# 04_-_Connectors.net
KiCad netlist of a schematic drawn in Altium Designer
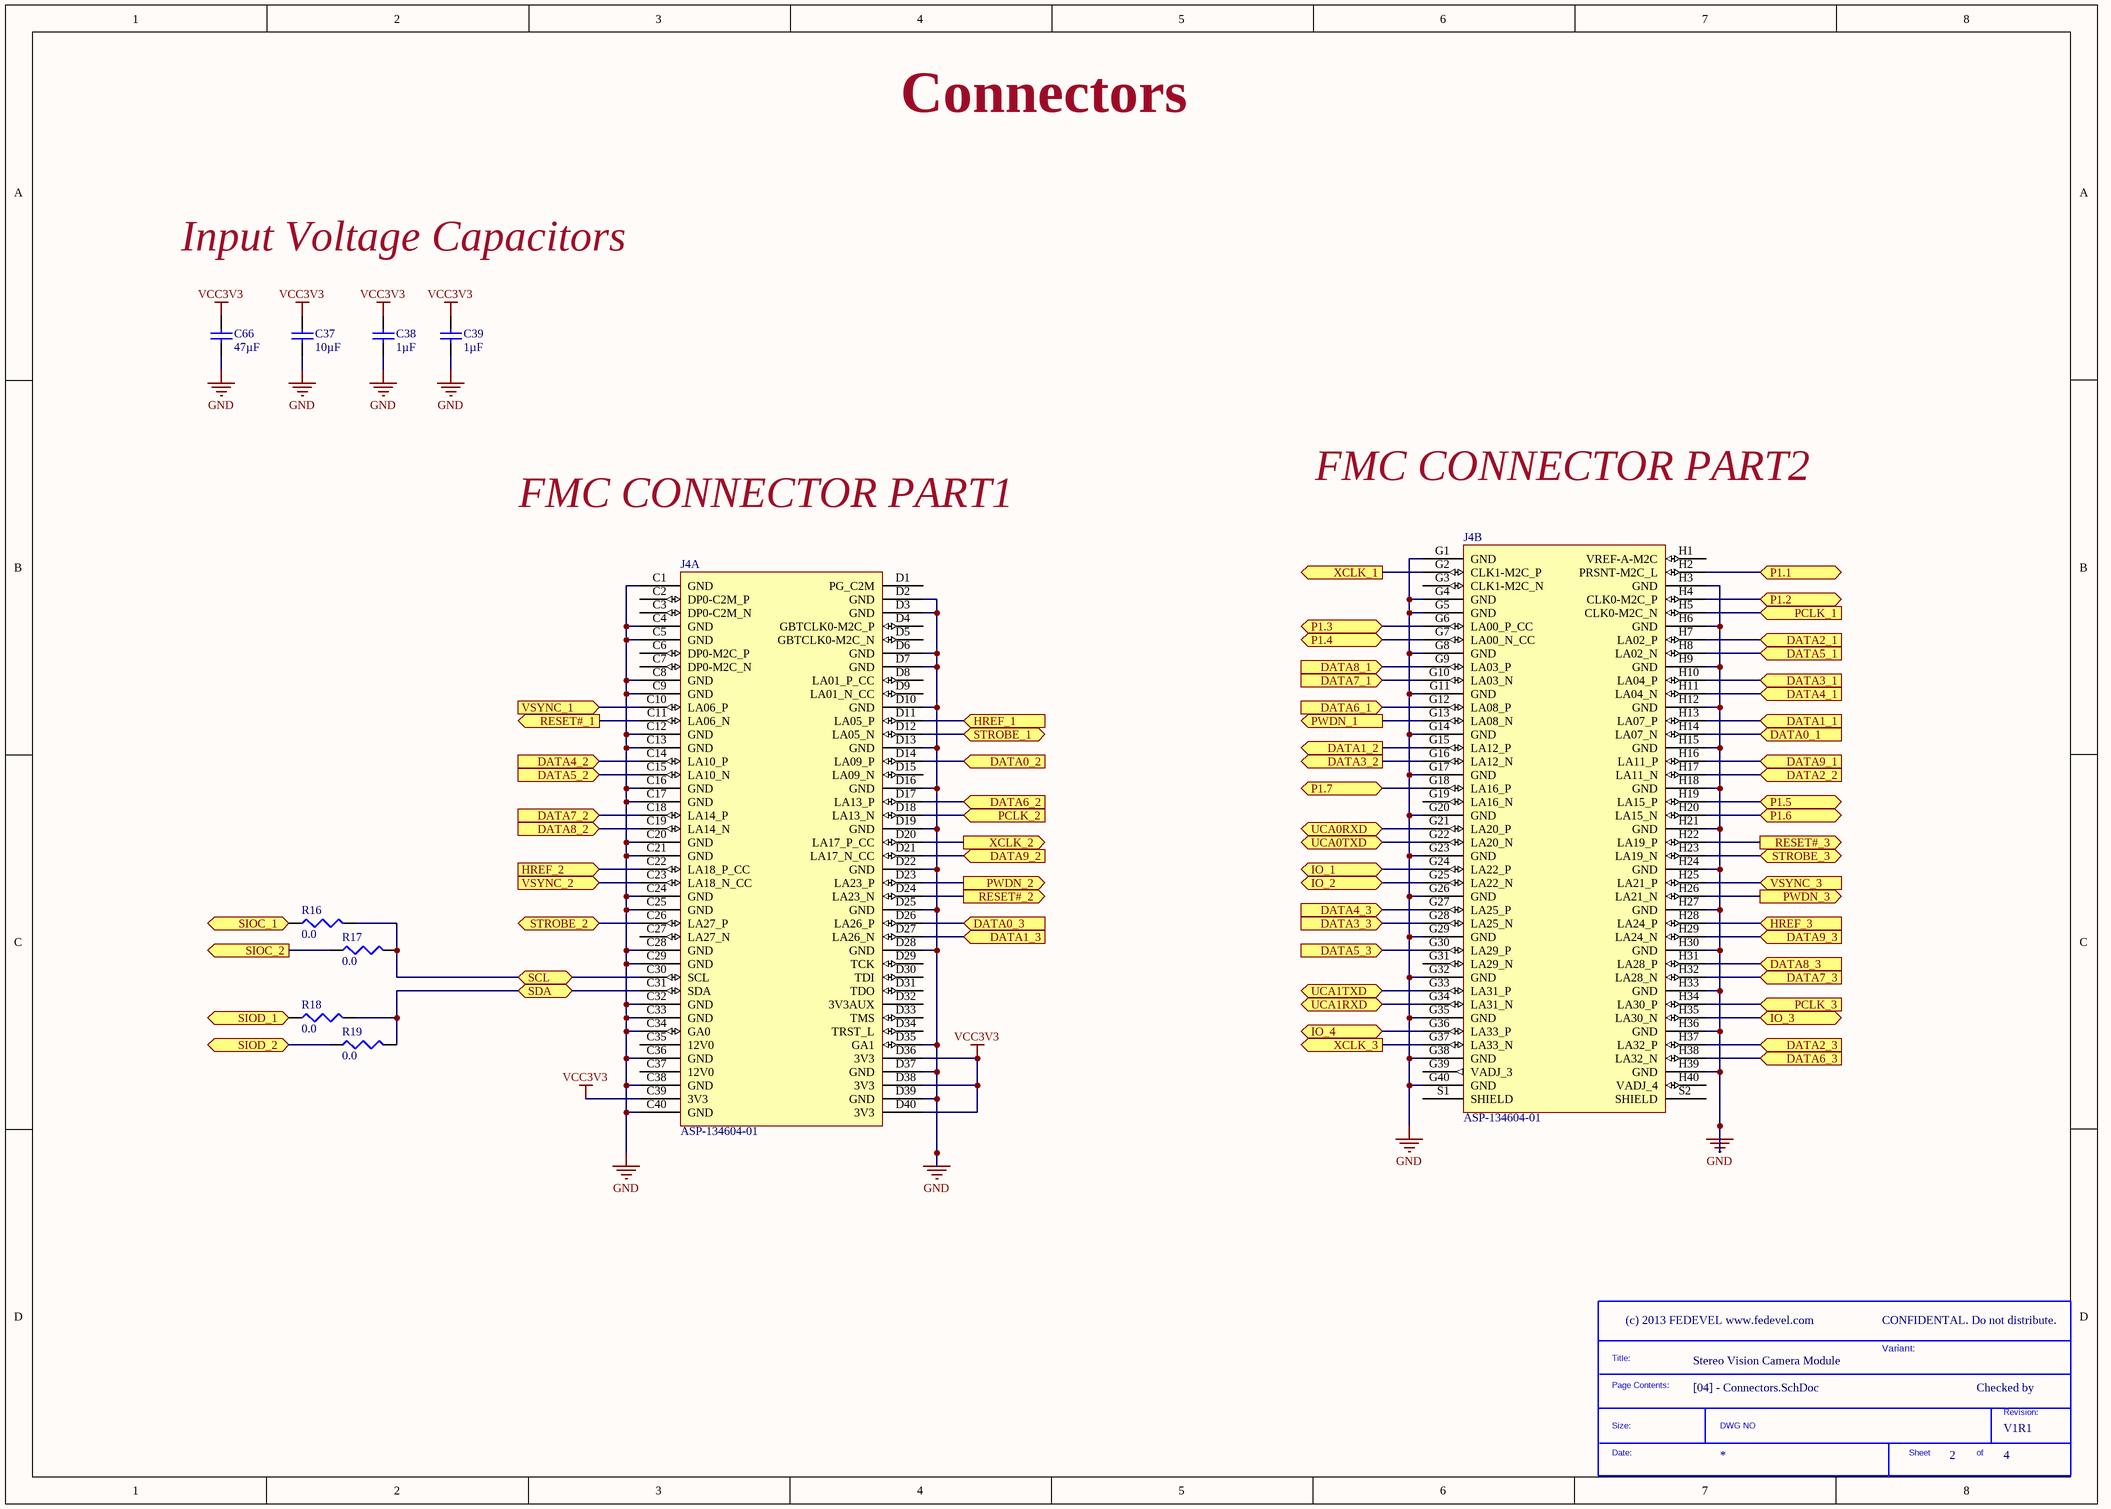
[diagram p0: [04] - Connectors.SchDoc]

(export (version "E")
  (design (tool "Eeschema 10.0.6"))
  (components
    (comp (ref "C37")
      (value "GRM21BR61E106KA73L")
      (footprint "CAP-0805")
      (description "CAP CER 10UF 25V X5R 0805")
      (fields
        (field (name "MANUFACTURER") "Murata Electronics North America")
        (field (name "TOLERANCE") "±10%")
        (field (name "CAPACITANCE") "10µF")
      )
      (libsource (lib "camera_module") (part "GRM21BR61E106KA73L"))
    )
    (comp (ref "C38")
      (value "GRM188R71C105KA12D")
      (footprint "CAP-0603")
      (description "CAP CER 1UF 16V X7R 0603")
      (fields
        (field (name "MANUFACTURER") "Murata Electronics North America")
        (field (name "TOLERANCE") "±10%")
        (field (name "CAPACITANCE") "1µF")
      )
      (libsource (lib "camera_module") (part "GRM188R71C105KA12D"))
    )
    (comp (ref "C39")
      (value "GRM188R71C105KA12D")
      (footprint "CAP-0603")
      (description "CAP CER 1UF 16V X7R 0603")
      (fields
        (field (name "MANUFACTURER") "Murata Electronics North America")
        (field (name "TOLERANCE") "±10%")
        (field (name "CAPACITANCE") "1µF")
      )
      (libsource (lib "camera_module") (part "GRM188R71C105KA12D"))
    )
    (comp (ref "C66")
      (value "GRM21BR60J476ME15L")
      (footprint "CAP-0805")
      (description "CAP CER 47UF 6.3V X5R 0805")
      (fields
        (field (name "MANUFACTURER") "Murata Electronics North America")
        (field (name "TOLERANCE") "±20%")
        (field (name "CAPACITANCE") "47µF")
      )
      (libsource (lib "camera_module") (part "GRM21BR60J476ME15L"))
    )
    (comp (ref "J4")
      (value "ASP-134604-01")
      (footprint "ASP-134604-01")
      (fields (field (name "MANUFACTURER") "SAMTEC"))
      (libsource (lib "camera_module") (part "ASP-134604-01"))
    )
    (comp (ref "R16")
      (value "ERJ-3GEY0R00V")
      (footprint "R0603")
      (description "RES SMD 0.0OHM JUMPER 1/10W 0603")
      (fields
        (field (name "MANUFACTURER") "Panasonic Electronic Components")
        (field (name "TOLERANCE") "Jumper")
        (field (name "RESISTANCE (OHMS)") "0.0")
      )
      (libsource (lib "camera_module") (part "ERJ-3GEY0R00V"))
    )
    (comp (ref "R17")
      (value "ERJ-3GEY0R00V")
      (footprint "R0603")
      (description "RES SMD 0.0OHM JUMPER 1/10W 0603")
      (fields
        (field (name "MANUFACTURER") "Panasonic Electronic Components")
        (field (name "TOLERANCE") "Jumper")
        (field (name "RESISTANCE (OHMS)") "0.0")
      )
      (libsource (lib "camera_module") (part "ERJ-3GEY0R00V"))
    )
    (comp (ref "R18")
      (value "ERJ-3GEY0R00V")
      (footprint "R0603")
      (description "RES SMD 0.0OHM JUMPER 1/10W 0603")
      (fields
        (field (name "MANUFACTURER") "Panasonic Electronic Components")
        (field (name "TOLERANCE") "Jumper")
        (field (name "RESISTANCE (OHMS)") "0.0")
      )
      (libsource (lib "camera_module") (part "ERJ-3GEY0R00V"))
    )
    (comp (ref "R19")
      (value "ERJ-3GEY0R00V")
      (footprint "R0603")
      (description "RES SMD 0.0OHM JUMPER 1/10W 0603")
      (fields
        (field (name "MANUFACTURER") "Panasonic Electronic Components")
        (field (name "TOLERANCE") "Jumper")
        (field (name "RESISTANCE (OHMS)") "0.0")
      )
      (libsource (lib "camera_module") (part "ERJ-3GEY0R00V"))
    )
  )
  (nets
    (net (code "1") (name "/DATA0_1") (class "Default")
      (node (ref "J4") (pin "H14") (pinfunction "LA07_N_H14") (pintype "bidirectional"))
    )
    (net (code "2") (name "/DATA0_2") (class "Default")
      (node (ref "J4") (pin "D14") (pinfunction "LA09_P_D14") (pintype "bidirectional"))
    )
    (net (code "3") (name "/DATA0_3") (class "Default")
      (node (ref "J4") (pin "D26") (pinfunction "LA26_P_D26") (pintype "bidirectional"))
    )
    (net (code "4") (name "/DATA1_1") (class "Default")
      (node (ref "J4") (pin "H13") (pinfunction "LA07_P_H13") (pintype "bidirectional"))
    )
    (net (code "5") (name "/DATA1_2") (class "Default")
      (node (ref "J4") (pin "G15") (pinfunction "LA12_P_G15") (pintype "bidirectional"))
    )
    (net (code "6") (name "/DATA1_3") (class "Default")
      (node (ref "J4") (pin "D27") (pinfunction "LA26_N_D27") (pintype "bidirectional"))
    )
    (net (code "7") (name "/DATA2_1") (class "Default")
      (node (ref "J4") (pin "H7") (pinfunction "LA02_P_H7") (pintype "bidirectional"))
    )
    (net (code "8") (name "/DATA2_2") (class "Default")
      (node (ref "J4") (pin "H17") (pinfunction "LA11_N_H17") (pintype "bidirectional"))
    )
    (net (code "9") (name "/DATA2_3") (class "Default")
      (node (ref "J4") (pin "H37") (pinfunction "LA32_P_H37") (pintype "bidirectional"))
    )
    (net (code "10") (name "/DATA3_1") (class "Default")
      (node (ref "J4") (pin "H10") (pinfunction "LA04_P_H10") (pintype "bidirectional"))
    )
    (net (code "11") (name "/DATA3_2") (class "Default")
      (node (ref "J4") (pin "G16") (pinfunction "LA12_N_G16") (pintype "bidirectional"))
    )
    (net (code "12") (name "/DATA3_3") (class "Default")
      (node (ref "J4") (pin "G28") (pinfunction "LA25_N_G28") (pintype "bidirectional"))
    )
    (net (code "13") (name "/DATA4_1") (class "Default")
      (node (ref "J4") (pin "H11") (pinfunction "LA04_N_H11") (pintype "bidirectional"))
    )
    (net (code "14") (name "/DATA4_2") (class "Default")
      (node (ref "J4") (pin "C14") (pinfunction "LA10_P_C14") (pintype "bidirectional"))
    )
    (net (code "15") (name "/DATA4_3") (class "Default")
      (node (ref "J4") (pin "G27") (pinfunction "LA25_P_G27") (pintype "bidirectional"))
    )
    (net (code "16") (name "/DATA5_1") (class "Default")
      (node (ref "J4") (pin "H8") (pinfunction "LA02_N_H8") (pintype "bidirectional"))
    )
    (net (code "17") (name "/DATA5_2") (class "Default")
      (node (ref "J4") (pin "C15") (pinfunction "LA10_N_C15") (pintype "bidirectional"))
    )
    (net (code "18") (name "/DATA5_3") (class "Default")
      (node (ref "J4") (pin "G30") (pinfunction "LA29_P_G30") (pintype "bidirectional"))
    )
    (net (code "19") (name "/DATA6_1") (class "Default")
      (node (ref "J4") (pin "G12") (pinfunction "LA08_P_G12") (pintype "bidirectional"))
    )
    (net (code "20") (name "/DATA6_2") (class "Default")
      (node (ref "J4") (pin "D17") (pinfunction "LA13_P_D17") (pintype "bidirectional"))
    )
    (net (code "21") (name "/DATA6_3") (class "Default")
      (node (ref "J4") (pin "H38") (pinfunction "LA32_N_H38") (pintype "bidirectional"))
    )
    (net (code "22") (name "/DATA7_1") (class "Default")
      (node (ref "J4") (pin "G10") (pinfunction "LA03_N_G10") (pintype "bidirectional"))
    )
    (net (code "23") (name "/DATA7_2") (class "Default")
      (node (ref "J4") (pin "C18") (pinfunction "LA14_P_C18") (pintype "bidirectional"))
    )
    (net (code "24") (name "/DATA7_3") (class "Default")
      (node (ref "J4") (pin "H32") (pinfunction "LA28_N_H32") (pintype "bidirectional"))
    )
    (net (code "25") (name "/DATA8_1") (class "Default")
      (node (ref "J4") (pin "G9") (pinfunction "LA03_P_G9") (pintype "bidirectional"))
    )
    (net (code "26") (name "/DATA8_2") (class "Default")
      (node (ref "J4") (pin "C19") (pinfunction "LA14_N_C19") (pintype "bidirectional"))
    )
    (net (code "27") (name "/DATA8_3") (class "Default")
      (node (ref "J4") (pin "H31") (pinfunction "LA28_P_H31") (pintype "bidirectional"))
    )
    (net (code "28") (name "/DATA9_1") (class "Default")
      (node (ref "J4") (pin "H16") (pinfunction "LA11_P_H16") (pintype "bidirectional"))
    )
    (net (code "29") (name "/DATA9_2") (class "Default")
      (node (ref "J4") (pin "D21") (pinfunction "LA17_N_CC_D21") (pintype "bidirectional"))
    )
    (net (code "30") (name "/DATA9_3") (class "Default")
      (node (ref "J4") (pin "H29") (pinfunction "LA24_N_H29") (pintype "bidirectional"))
    )
    (net (code "31") (name "/HREF_1") (class "Default")
      (node (ref "J4") (pin "D11") (pinfunction "LA05_P_D11") (pintype "bidirectional"))
    )
    (net (code "32") (name "/HREF_2") (class "Default")
      (node (ref "J4") (pin "C22") (pinfunction "LA18_P_CC_C22") (pintype "bidirectional"))
    )
    (net (code "33") (name "/HREF_3") (class "Default")
      (node (ref "J4") (pin "H28") (pinfunction "LA24_P_H28") (pintype "bidirectional"))
    )
    (net (code "34") (name "/IO_1") (class "Default")
      (node (ref "J4") (pin "G24") (pinfunction "LA22_P_G24") (pintype "bidirectional"))
    )
    (net (code "35") (name "/IO_2") (class "Default")
      (node (ref "J4") (pin "G25") (pinfunction "LA22_N_G25") (pintype "bidirectional"))
    )
    (net (code "36") (name "/IO_3") (class "Default")
      (node (ref "J4") (pin "H35") (pinfunction "LA30_N_H35") (pintype "bidirectional"))
    )
    (net (code "37") (name "/IO_4") (class "Default")
      (node (ref "J4") (pin "G36") (pinfunction "LA33_P_G36") (pintype "bidirectional"))
    )
    (net (code "38") (name "/P1.1") (class "Default")
      (node (ref "J4") (pin "H2") (pinfunction "PRSNT-M2C_L_H2") (pintype "bidirectional"))
    )
    (net (code "39") (name "/P1.2") (class "Default")
      (node (ref "J4") (pin "H4") (pinfunction "CLK0-M2C_P_H4") (pintype "bidirectional"))
    )
    (net (code "40") (name "/P1.3") (class "Default")
      (node (ref "J4") (pin "G6") (pinfunction "LA00_P_CC_G6") (pintype "bidirectional"))
    )
    (net (code "41") (name "/P1.4") (class "Default")
      (node (ref "J4") (pin "G7") (pinfunction "LA00_N_CC_G7") (pintype "bidirectional"))
    )
    (net (code "42") (name "/P1.5") (class "Default")
      (node (ref "J4") (pin "H19") (pinfunction "LA15_P_H19") (pintype "bidirectional"))
    )
    (net (code "43") (name "/P1.6") (class "Default")
      (node (ref "J4") (pin "H20") (pinfunction "LA15_N_H20") (pintype "bidirectional"))
    )
    (net (code "44") (name "/P1.7") (class "Default")
      (node (ref "J4") (pin "G18") (pinfunction "LA16_P_G18") (pintype "bidirectional"))
    )
    (net (code "45") (name "/PCLK_1") (class "Default")
      (node (ref "J4") (pin "H5") (pinfunction "CLK0-M2C_N_H5") (pintype "bidirectional"))
    )
    (net (code "46") (name "/PCLK_2") (class "Default")
      (node (ref "J4") (pin "D18") (pinfunction "LA13_N_D18") (pintype "bidirectional"))
    )
    (net (code "47") (name "/PCLK_3") (class "Default")
      (node (ref "J4") (pin "H34") (pinfunction "LA30_P_H34") (pintype "bidirectional"))
    )
    (net (code "48") (name "/PWDN_1") (class "Default")
      (node (ref "J4") (pin "G13") (pinfunction "LA08_N_G13") (pintype "bidirectional"))
    )
    (net (code "49") (name "/PWDN_2") (class "Default")
      (node (ref "J4") (pin "D23") (pinfunction "LA23_P_D23") (pintype "bidirectional"))
    )
    (net (code "50") (name "/PWDN_3") (class "Default")
      (node (ref "J4") (pin "H26") (pinfunction "LA21_N_H26") (pintype "bidirectional"))
    )
    (net (code "51") (name "/RESET#_1") (class "Default")
      (node (ref "J4") (pin "C11") (pinfunction "LA06_N_C11") (pintype "bidirectional"))
    )
    (net (code "52") (name "/RESET#_2") (class "Default")
      (node (ref "J4") (pin "D24") (pinfunction "LA23_N_D24") (pintype "bidirectional"))
    )
    (net (code "53") (name "/RESET#_3") (class "Default")
      (node (ref "J4") (pin "H22") (pinfunction "LA19_P_H22") (pintype "bidirectional"))
    )
    (net (code "54") (name "/SCL") (class "Default")
      (node (ref "J4") (pin "C30") (pinfunction "SCL_C30") (pintype "bidirectional"))
      (node (ref "R16") (pin "2") (pinfunction "2_2") (pintype "passive"))
      (node (ref "R17") (pin "2") (pinfunction "2_2") (pintype "passive"))
    )
    (net (code "55") (name "/SDA") (class "Default")
      (node (ref "J4") (pin "C31") (pinfunction "SDA_C31") (pintype "bidirectional"))
      (node (ref "R18") (pin "2") (pinfunction "2_2") (pintype "passive"))
      (node (ref "R19") (pin "2") (pinfunction "2_2") (pintype "passive"))
    )
    (net (code "56") (name "/SIOC_1") (class "Default")
      (node (ref "R16") (pin "1") (pinfunction "1_1") (pintype "passive"))
    )
    (net (code "57") (name "/SIOC_2") (class "Default")
      (node (ref "R17") (pin "1") (pinfunction "1_1") (pintype "passive"))
    )
    (net (code "58") (name "/SIOD_1") (class "Default")
      (node (ref "R18") (pin "1") (pinfunction "1_1") (pintype "passive"))
    )
    (net (code "59") (name "/SIOD_2") (class "Default")
      (node (ref "R19") (pin "1") (pinfunction "1_1") (pintype "passive"))
    )
    (net (code "60") (name "/STROBE_1") (class "Default")
      (node (ref "J4") (pin "D12") (pinfunction "LA05_N_D12") (pintype "bidirectional"))
    )
    (net (code "61") (name "/STROBE_2") (class "Default")
      (node (ref "J4") (pin "C26") (pinfunction "LA27_P_C26") (pintype "bidirectional"))
    )
    (net (code "62") (name "/STROBE_3") (class "Default")
      (node (ref "J4") (pin "H23") (pinfunction "LA19_N_H23") (pintype "bidirectional"))
    )
    (net (code "63") (name "/UCA0RXD") (class "Default")
      (node (ref "J4") (pin "G21") (pinfunction "LA20_P_G21") (pintype "bidirectional"))
    )
    (net (code "64") (name "/UCA0TXD") (class "Default")
      (node (ref "J4") (pin "G22") (pinfunction "LA20_N_G22") (pintype "bidirectional"))
    )
    (net (code "65") (name "/UCA1RXD") (class "Default")
      (node (ref "J4") (pin "G34") (pinfunction "LA31_N_G34") (pintype "bidirectional"))
    )
    (net (code "66") (name "/UCA1TXD") (class "Default")
      (node (ref "J4") (pin "G33") (pinfunction "LA31_P_G33") (pintype "bidirectional"))
    )
    (net (code "67") (name "/VSYNC_1") (class "Default")
      (node (ref "J4") (pin "C10") (pinfunction "LA06_P_C10") (pintype "bidirectional"))
    )
    (net (code "68") (name "/VSYNC_2") (class "Default")
      (node (ref "J4") (pin "C23") (pinfunction "LA18_N_CC_C23") (pintype "bidirectional"))
    )
    (net (code "69") (name "/VSYNC_3") (class "Default")
      (node (ref "J4") (pin "H25") (pinfunction "LA21_P_H25") (pintype "bidirectional"))
    )
    (net (code "70") (name "/XCLK_1") (class "Default")
      (node (ref "J4") (pin "G2") (pinfunction "CLK1-M2C_P_G2") (pintype "bidirectional"))
    )
    (net (code "71") (name "/XCLK_2") (class "Default")
      (node (ref "J4") (pin "D20") (pinfunction "LA17_P_CC_D20") (pintype "bidirectional"))
    )
    (net (code "72") (name "/XCLK_3") (class "Default")
      (node (ref "J4") (pin "G37") (pinfunction "LA33_N_G37") (pintype "bidirectional"))
    )
    (net (code "73") (name "GND") (class "Default")
      (node (ref "C37") (pin "2") (pinfunction "2_2") (pintype "passive"))
      (node (ref "C38") (pin "2") (pinfunction "2_2") (pintype "passive"))
      (node (ref "C39") (pin "2") (pinfunction "2_2") (pintype "passive"))
      (node (ref "C66") (pin "2") (pinfunction "2_2") (pintype "passive"))
      (node (ref "J4") (pin "C1") (pinfunction "GND_C1") (pintype "power_in"))
      (node (ref "J4") (pin "C12") (pinfunction "GND_C12") (pintype "power_in"))
      (node (ref "J4") (pin "C13") (pinfunction "GND_C13") (pintype "power_in"))
      (node (ref "J4") (pin "C16") (pinfunction "GND_C16") (pintype "power_in"))
      (node (ref "J4") (pin "C17") (pinfunction "GND_C17") (pintype "power_in"))
      (node (ref "J4") (pin "C20") (pinfunction "GND_C20") (pintype "power_in"))
      (node (ref "J4") (pin "C21") (pinfunction "GND_C21") (pintype "power_in"))
      (node (ref "J4") (pin "C24") (pinfunction "GND_C24") (pintype "power_in"))
      (node (ref "J4") (pin "C25") (pinfunction "GND_C25") (pintype "power_in"))
      (node (ref "J4") (pin "C28") (pinfunction "GND_C28") (pintype "power_in"))
      (node (ref "J4") (pin "C29") (pinfunction "GND_C29") (pintype "power_in"))
      (node (ref "J4") (pin "C32") (pinfunction "GND_C32") (pintype "power_in"))
      (node (ref "J4") (pin "C33") (pinfunction "GND_C33") (pintype "power_in"))
      (node (ref "J4") (pin "C34") (pinfunction "GA0_C34") (pintype "bidirectional"))
      (node (ref "J4") (pin "C36") (pinfunction "GND_C36") (pintype "power_in"))
      (node (ref "J4") (pin "C38") (pinfunction "GND_C38") (pintype "power_in"))
      (node (ref "J4") (pin "C4") (pinfunction "GND_C4") (pintype "power_in"))
      (node (ref "J4") (pin "C40") (pinfunction "GND_C40") (pintype "power_in"))
      (node (ref "J4") (pin "C5") (pinfunction "GND_C5") (pintype "power_in"))
      (node (ref "J4") (pin "C8") (pinfunction "GND_C8") (pintype "power_in"))
      (node (ref "J4") (pin "C9") (pinfunction "GND_C9") (pintype "power_in"))
      (node (ref "J4") (pin "D10") (pinfunction "GND_D10") (pintype "power_in"))
      (node (ref "J4") (pin "D13") (pinfunction "GND_D13") (pintype "power_in"))
      (node (ref "J4") (pin "D16") (pinfunction "GND_D16") (pintype "power_in"))
      (node (ref "J4") (pin "D19") (pinfunction "GND_D19") (pintype "power_in"))
      (node (ref "J4") (pin "D2") (pinfunction "GND_D2") (pintype "power_in"))
      (node (ref "J4") (pin "D22") (pinfunction "GND_D22") (pintype "power_in"))
      (node (ref "J4") (pin "D25") (pinfunction "GND_D25") (pintype "power_in"))
      (node (ref "J4") (pin "D28") (pinfunction "GND_D28") (pintype "power_in"))
      (node (ref "J4") (pin "D3") (pinfunction "GND_D3") (pintype "power_in"))
      (node (ref "J4") (pin "D35") (pinfunction "GA1_D35") (pintype "bidirectional"))
      (node (ref "J4") (pin "D37") (pinfunction "GND_D37") (pintype "power_in"))
      (node (ref "J4") (pin "D39") (pinfunction "GND_D39") (pintype "power_in"))
      (node (ref "J4") (pin "D6") (pinfunction "GND_D6") (pintype "power_in"))
      (node (ref "J4") (pin "D7") (pinfunction "GND_D7") (pintype "power_in"))
      (node (ref "J4") (pin "G1") (pinfunction "GND_G1") (pintype "power_in"))
      (node (ref "J4") (pin "G11") (pinfunction "GND_G11") (pintype "power_in"))
      (node (ref "J4") (pin "G14") (pinfunction "GND_G14") (pintype "power_in"))
      (node (ref "J4") (pin "G17") (pinfunction "GND_G17") (pintype "power_in"))
      (node (ref "J4") (pin "G20") (pinfunction "GND_G20") (pintype "power_in"))
      (node (ref "J4") (pin "G23") (pinfunction "GND_G23") (pintype "power_in"))
      (node (ref "J4") (pin "G26") (pinfunction "GND_G26") (pintype "power_in"))
      (node (ref "J4") (pin "G29") (pinfunction "GND_G29") (pintype "power_in"))
      (node (ref "J4") (pin "G32") (pinfunction "GND_G32") (pintype "power_in"))
      (node (ref "J4") (pin "G35") (pinfunction "GND_G35") (pintype "power_in"))
      (node (ref "J4") (pin "G38") (pinfunction "GND_G38") (pintype "power_in"))
      (node (ref "J4") (pin "G4") (pinfunction "GND_G4") (pintype "power_in"))
      (node (ref "J4") (pin "G40") (pinfunction "GND_G40") (pintype "power_in"))
      (node (ref "J4") (pin "G5") (pinfunction "GND_G5") (pintype "power_in"))
      (node (ref "J4") (pin "G8") (pinfunction "GND_G8") (pintype "power_in"))
      (node (ref "J4") (pin "H12") (pinfunction "GND_H12") (pintype "power_in"))
      (node (ref "J4") (pin "H15") (pinfunction "GND_H15") (pintype "power_in"))
      (node (ref "J4") (pin "H18") (pinfunction "GND_H18") (pintype "power_in"))
      (node (ref "J4") (pin "H21") (pinfunction "GND_H21") (pintype "power_in"))
      (node (ref "J4") (pin "H24") (pinfunction "GND_H24") (pintype "power_in"))
      (node (ref "J4") (pin "H27") (pinfunction "GND_H27") (pintype "power_in"))
      (node (ref "J4") (pin "H3") (pinfunction "GND_H3") (pintype "power_in"))
      (node (ref "J4") (pin "H30") (pinfunction "GND_H30") (pintype "power_in"))
      (node (ref "J4") (pin "H33") (pinfunction "GND_H33") (pintype "power_in"))
      (node (ref "J4") (pin "H36") (pinfunction "GND_H36") (pintype "power_in"))
      (node (ref "J4") (pin "H39") (pinfunction "GND_H39") (pintype "power_in"))
      (node (ref "J4") (pin "H6") (pinfunction "GND_H6") (pintype "power_in"))
      (node (ref "J4") (pin "H9") (pinfunction "GND_H9") (pintype "power_in"))
    )
    (net (code "74") (name "VCC3V3") (class "Default")
      (node (ref "C37") (pin "1") (pinfunction "1_1") (pintype "passive"))
      (node (ref "C38") (pin "1") (pinfunction "1_1") (pintype "passive"))
      (node (ref "C39") (pin "1") (pinfunction "1_1") (pintype "passive"))
      (node (ref "C66") (pin "1") (pinfunction "1_1") (pintype "passive"))
      (node (ref "J4") (pin "C39") (pinfunction "3V3_C39") (pintype "power_in"))
      (node (ref "J4") (pin "D36") (pinfunction "3V3_D36") (pintype "power_in"))
      (node (ref "J4") (pin "D38") (pinfunction "3V3_D38") (pintype "power_in"))
      (node (ref "J4") (pin "D40") (pinfunction "3V3_D40") (pintype "power_in"))
    )
    (net (code "75") (name "unconnected-(J4A-3V3AUX-PadD32)") (class "Default")
      (node (ref "J4") (pin "D32") (pinfunction "3V3AUX_D32") (pintype "power_in"))
    )
    (net (code "76") (name "unconnected-(J4A-12V0-PadC35)") (class "Default")
      (node (ref "J4") (pin "C35") (pinfunction "12V0_C35") (pintype "power_in"))
    )
    (net (code "77") (name "unconnected-(J4A-12V0-PadC37)") (class "Default")
      (node (ref "J4") (pin "C37") (pinfunction "12V0_C37") (pintype "power_in"))
    )
    (net (code "78") (name "unconnected-(J4A-DP0-C2M_N-PadC3)") (class "Default")
      (node (ref "J4") (pin "C3") (pinfunction "DP0-C2M_N_C3") (pintype "bidirectional"))
    )
    (net (code "79") (name "unconnected-(J4A-DP0-C2M_P-PadC2)") (class "Default")
      (node (ref "J4") (pin "C2") (pinfunction "DP0-C2M_P_C2") (pintype "bidirectional"))
    )
    (net (code "80") (name "unconnected-(J4A-DP0-M2C_N-PadC7)") (class "Default")
      (node (ref "J4") (pin "C7") (pinfunction "DP0-M2C_N_C7") (pintype "bidirectional"))
    )
    (net (code "81") (name "unconnected-(J4A-DP0-M2C_P-PadC6)") (class "Default")
      (node (ref "J4") (pin "C6") (pinfunction "DP0-M2C_P_C6") (pintype "bidirectional"))
    )
    (net (code "82") (name "unconnected-(J4A-GBTCLK0-M2C_N-PadD5)") (class "Default")
      (node (ref "J4") (pin "D5") (pinfunction "GBTCLK0-M2C_N_D5") (pintype "bidirectional"))
    )
    (net (code "83") (name "unconnected-(J4A-GBTCLK0-M2C_P-PadD4)") (class "Default")
      (node (ref "J4") (pin "D4") (pinfunction "GBTCLK0-M2C_P_D4") (pintype "bidirectional"))
    )
    (net (code "84") (name "unconnected-(J4A-LA01_N_CC-PadD9)") (class "Default")
      (node (ref "J4") (pin "D9") (pinfunction "LA01_N_CC_D9") (pintype "bidirectional"))
    )
    (net (code "85") (name "unconnected-(J4A-LA01_P_CC-PadD8)") (class "Default")
      (node (ref "J4") (pin "D8") (pinfunction "LA01_P_CC_D8") (pintype "bidirectional"))
    )
    (net (code "86") (name "unconnected-(J4A-LA09_N-PadD15)") (class "Default")
      (node (ref "J4") (pin "D15") (pinfunction "LA09_N_D15") (pintype "bidirectional"))
    )
    (net (code "87") (name "unconnected-(J4A-LA27_N-PadC27)") (class "Default")
      (node (ref "J4") (pin "C27") (pinfunction "LA27_N_C27") (pintype "bidirectional"))
    )
    (net (code "88") (name "unconnected-(J4A-PG_C2M-PadD1)") (class "Default")
      (node (ref "J4") (pin "D1") (pinfunction "PG_C2M_D1") (pintype "passive"))
    )
    (net (code "89") (name "unconnected-(J4A-TCK-PadD29)") (class "Default")
      (node (ref "J4") (pin "D29") (pinfunction "TCK_D29") (pintype "bidirectional"))
    )
    (net (code "90") (name "unconnected-(J4A-TDI-PadD30)") (class "Default")
      (node (ref "J4") (pin "D30") (pinfunction "TDI_D30") (pintype "bidirectional"))
    )
    (net (code "91") (name "unconnected-(J4A-TDO-PadD31)") (class "Default")
      (node (ref "J4") (pin "D31") (pinfunction "TDO_D31") (pintype "bidirectional"))
    )
    (net (code "92") (name "unconnected-(J4A-TMS-PadD33)") (class "Default")
      (node (ref "J4") (pin "D33") (pinfunction "TMS_D33") (pintype "bidirectional"))
    )
    (net (code "93") (name "unconnected-(J4A-TRST_L-PadD34)") (class "Default")
      (node (ref "J4") (pin "D34") (pinfunction "TRST_L_D34") (pintype "bidirectional"))
    )
    (net (code "94") (name "unconnected-(J4B-CLK1-M2C_N-PadG3)") (class "Default")
      (node (ref "J4") (pin "G3") (pinfunction "CLK1-M2C_N_G3") (pintype "bidirectional"))
    )
    (net (code "95") (name "unconnected-(J4B-LA16_N-PadG19)") (class "Default")
      (node (ref "J4") (pin "G19") (pinfunction "LA16_N_G19") (pintype "bidirectional"))
    )
    (net (code "96") (name "unconnected-(J4B-LA29_N-PadG31)") (class "Default")
      (node (ref "J4") (pin "G31") (pinfunction "LA29_N_G31") (pintype "bidirectional"))
    )
    (net (code "97") (name "unconnected-(J4B-SHIELD-PadS1)") (class "Default")
      (node (ref "J4") (pin "S1") (pinfunction "SHIELD_S1") (pintype "power_in"))
    )
    (net (code "98") (name "unconnected-(J4B-SHIELD-PadS2)") (class "Default")
      (node (ref "J4") (pin "S2") (pinfunction "SHIELD_S2") (pintype "power_in"))
    )
    (net (code "99") (name "unconnected-(J4B-VADJ_3-PadG39)") (class "Default")
      (node (ref "J4") (pin "G39") (pinfunction "VADJ_3_G39") (pintype "output"))
    )
    (net (code "100") (name "unconnected-(J4B-VADJ_4-PadH40)") (class "Default")
      (node (ref "J4") (pin "H40") (pinfunction "VADJ_4_H40") (pintype "bidirectional"))
    )
    (net (code "101") (name "unconnected-(J4B-VREF-A-M2C-PadH1)") (class "Default")
      (node (ref "J4") (pin "H1") (pinfunction "VREF-A-M2C_H1") (pintype "bidirectional"))
    )
  )
)
